# Dynamixel.net
KiCad netlist of a schematic drawn in EAGLE
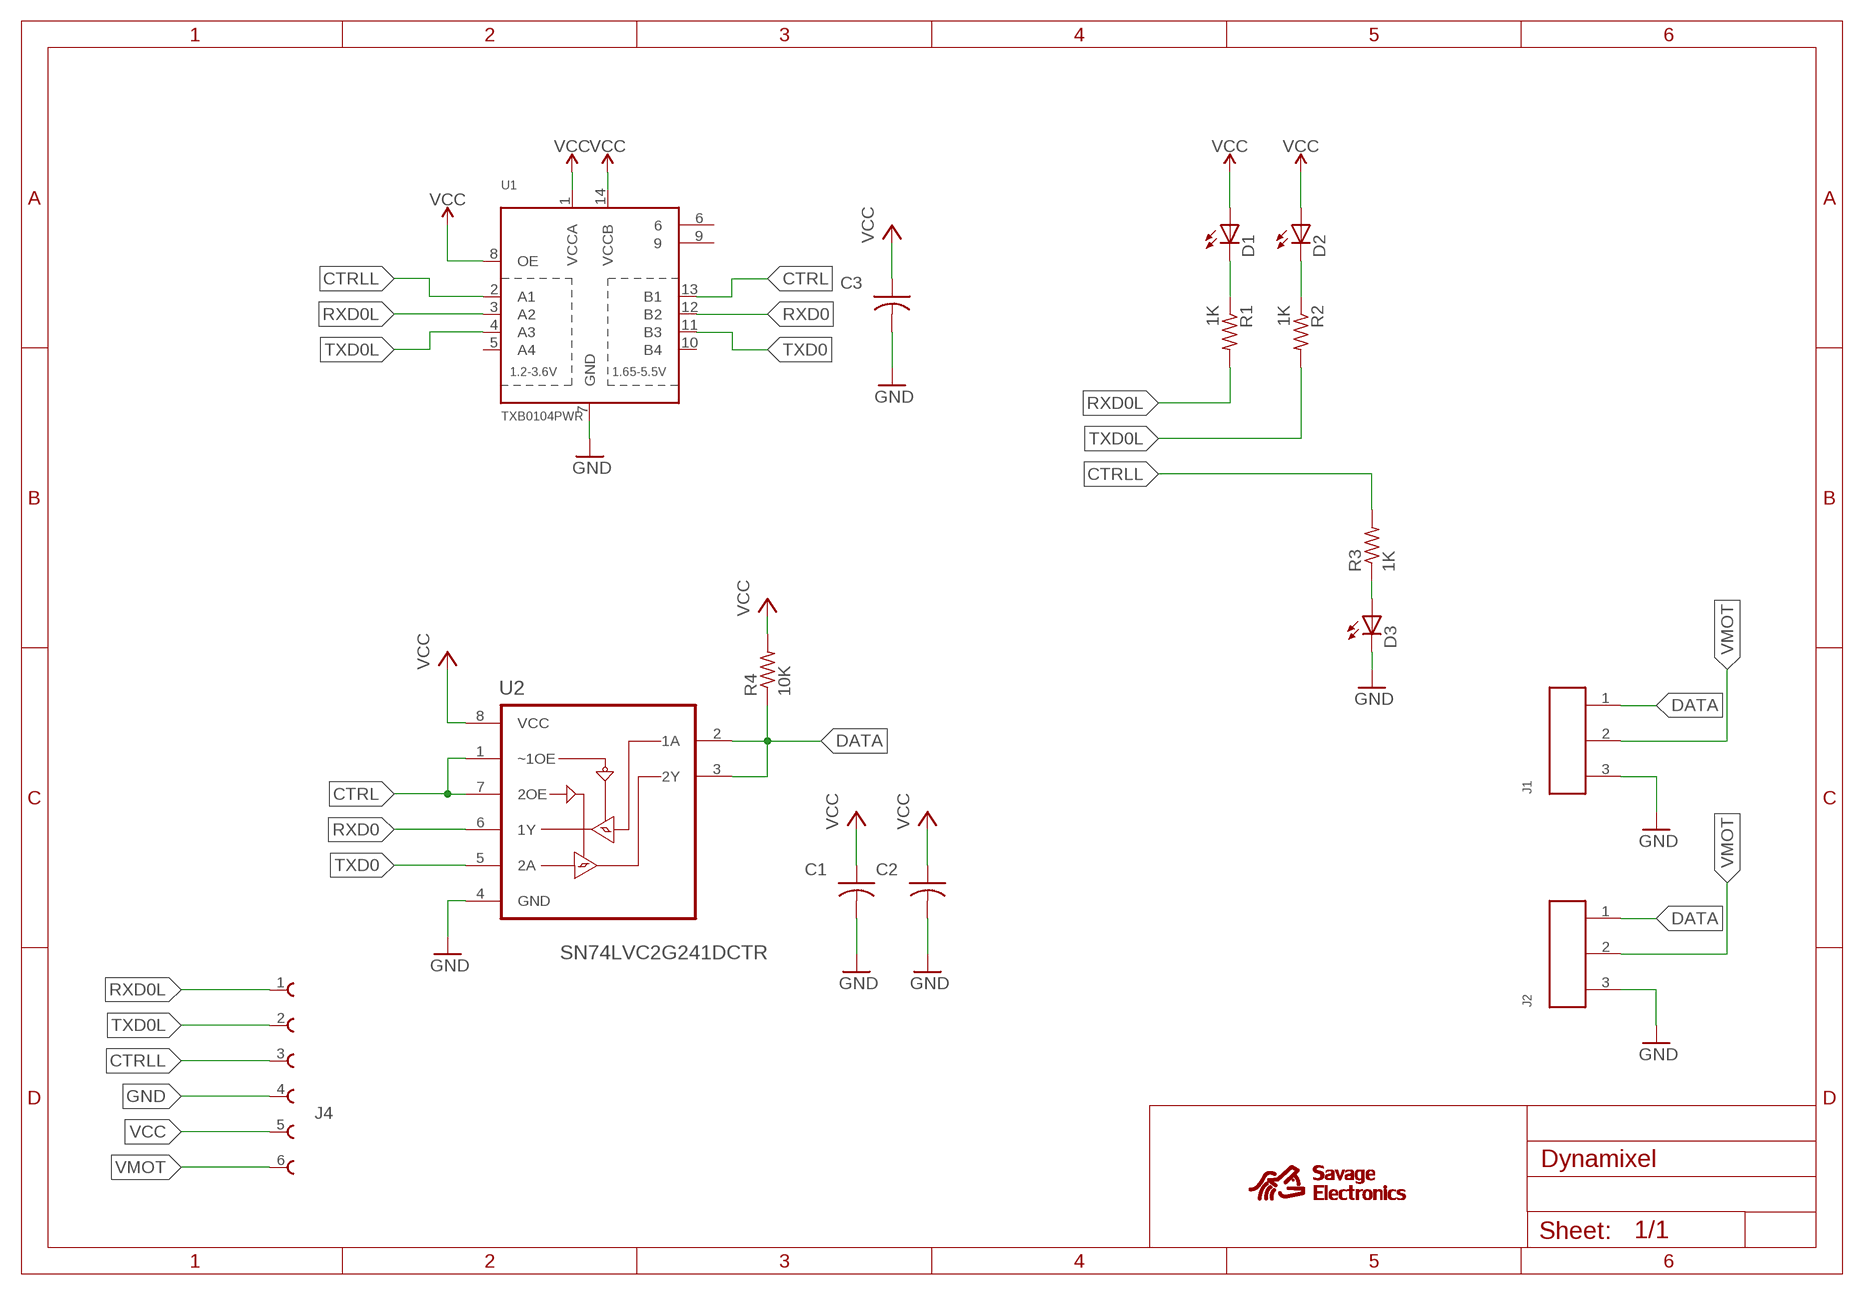
[diagram p0: schematic, sheet 1]

(export (version "E")
  (design (tool "Eeschema 10.0.6"))
  (components
    (comp (ref "C1")
      (value "1uF")
      (footprint "eagle-import:C0805")
      (libsource (lib "eagle-import") (part "C-USC0805"))
    )
    (comp (ref "C2")
      (value "1uF")
      (footprint "eagle-import:C0805")
      (libsource (lib "eagle-import") (part "C-USC0805"))
    )
    (comp (ref "C3")
      (value "1uF")
      (footprint "eagle-import:C0805")
      (libsource (lib "eagle-import") (part "C-USC0805"))
    )
    (comp (ref "D1")
      (value "LEDCHIP-LED0805")
      (footprint "eagle-import:CHIP-LED0805")
      (libsource (lib "eagle-import") (part "LEDCHIP-LED0805"))
    )
    (comp (ref "D2")
      (value "LEDCHIP-LED0805")
      (footprint "eagle-import:CHIP-LED0805")
      (libsource (lib "eagle-import") (part "LEDCHIP-LED0805"))
    )
    (comp (ref "D3")
      (value "LEDCHIP-LED0805")
      (footprint "eagle-import:CHIP-LED0805")
      (libsource (lib "eagle-import") (part "LEDCHIP-LED0805"))
    )
    (comp (ref "J1")
      (value "62000311722")
      (footprint "eagle-import:62000311722")
      (libsource (lib "eagle-import") (part "62000311722"))
    )
    (comp (ref "J2")
      (value "64600311622")
      (footprint "eagle-import:64600311622")
      (libsource (lib "eagle-import") (part "64600311622"))
    )
    (comp (ref "J4")
      (value "61300611121")
      (footprint "eagle-import:61300611121")
      (libsource (lib "eagle-import") (part "61300611121"))
    )
    (comp (ref "R1")
      (value "1K")
      (footprint "eagle-import:R0805")
      (libsource (lib "eagle-import") (part "R-US_R0805"))
    )
    (comp (ref "R2")
      (value "1K")
      (footprint "eagle-import:R0805")
      (libsource (lib "eagle-import") (part "R-US_R0805"))
    )
    (comp (ref "R3")
      (value "1K")
      (footprint "eagle-import:R0805")
      (libsource (lib "eagle-import") (part "R-US_R0805"))
    )
    (comp (ref "R4")
      (value "10K")
      (footprint "eagle-import:R0805")
      (libsource (lib "eagle-import") (part "R-US_R0805"))
    )
    (comp (ref "U$2")
      (value "SE_SMALL_SILK")
      (footprint "eagle-import:SE_SMALL_SILK")
      (libsource (lib "eagle-import") (part "SE_SMALL_SILK"))
    )
    (comp (ref "U$3")
      (value "SE_SMALL_FSILK")
      (footprint "eagle-import:SE_SMALL_FACESILK")
      (libsource (lib "eagle-import") (part "SE_SMALL_FSILK"))
    )
    (comp (ref "U1")
      (value "TXB0104PWR")
      (footprint "eagle-import:TSSOP14")
      (libsource (lib "eagle-import") (part "TXB0104PWR"))
    )
    (comp (ref "U2")
      (value "SN74LVC2G241DCTR")
      (footprint "eagle-import:SOP65P400X130-8N")
      (fields (field (name "MF") "Texas Instruments") (field (name "MP") "SN74LVC2G241"))
      (libsource (lib "eagle-import") (part "SN74LVC2G241"))
    )
  )
  (nets
    (net (code "1") (name "CTRL") (class "Default")
      (node (ref "U1") (pin "13") (pinfunction "B1_13") (pintype "bidirectional"))
      (node (ref "U2") (pin "1") (pinfunction "~{1OE}_1") (pintype "input"))
      (node (ref "U2") (pin "7") (pinfunction "2OE_7") (pintype "input"))
    )
    (net (code "2") (name "CTRLL") (class "Default")
      (node (ref "J4") (pin "3") (pinfunction "3_3") (pintype "passive"))
      (node (ref "R3") (pin "2") (pinfunction "2_2") (pintype "passive"))
      (node (ref "U1") (pin "2") (pinfunction "A1_2") (pintype "bidirectional"))
    )
    (net (code "3") (name "DATA") (class "Default")
      (node (ref "J1") (pin "1") (pinfunction "1_1") (pintype "passive"))
      (node (ref "J2") (pin "1") (pinfunction "1_1") (pintype "passive"))
      (node (ref "R4") (pin "1") (pinfunction "1_1") (pintype "passive"))
      (node (ref "U2") (pin "2") (pinfunction "1A_2") (pintype "input"))
      (node (ref "U2") (pin "3") (pinfunction "2Y_3") (pintype "output"))
    )
    (net (code "4") (name "GND") (class "Default")
      (node (ref "C1") (pin "2") (pinfunction "2_2") (pintype "passive"))
      (node (ref "C2") (pin "2") (pinfunction "2_2") (pintype "passive"))
      (node (ref "C3") (pin "2") (pinfunction "2_2") (pintype "passive"))
      (node (ref "D3") (pin "C") (pinfunction "C_C") (pintype "passive"))
      (node (ref "J1") (pin "3") (pinfunction "3_3") (pintype "passive"))
      (node (ref "J2") (pin "3") (pinfunction "3_3") (pintype "passive"))
      (node (ref "J4") (pin "4") (pinfunction "4_4") (pintype "passive"))
      (node (ref "U1") (pin "7") (pinfunction "GND_7") (pintype "bidirectional"))
      (node (ref "U2") (pin "4") (pinfunction "GND_4") (pintype "passive"))
    )
    (net (code "5") (name "Net-(D1-PadC)") (class "Default")
      (node (ref "D1") (pin "C") (pinfunction "C_C") (pintype "passive"))
      (node (ref "R1") (pin "1") (pinfunction "1_1") (pintype "passive"))
    )
    (net (code "6") (name "Net-(D2-PadC)") (class "Default")
      (node (ref "D2") (pin "C") (pinfunction "C_C") (pintype "passive"))
      (node (ref "R2") (pin "1") (pinfunction "1_1") (pintype "passive"))
    )
    (net (code "7") (name "Net-(D3-PadA)") (class "Default")
      (node (ref "D3") (pin "A") (pinfunction "A_A") (pintype "passive"))
      (node (ref "R3") (pin "1") (pinfunction "1_1") (pintype "passive"))
    )
    (net (code "8") (name "RXD0") (class "Default")
      (node (ref "U1") (pin "12") (pinfunction "B2_12") (pintype "bidirectional"))
      (node (ref "U2") (pin "6") (pinfunction "1Y_6") (pintype "output"))
    )
    (net (code "9") (name "RXD0L") (class "Default")
      (node (ref "J4") (pin "1") (pinfunction "1_1") (pintype "passive"))
      (node (ref "R1") (pin "2") (pinfunction "2_2") (pintype "passive"))
      (node (ref "U1") (pin "3") (pinfunction "A2_3") (pintype "bidirectional"))
    )
    (net (code "10") (name "TXD0") (class "Default")
      (node (ref "U1") (pin "11") (pinfunction "B3_11") (pintype "bidirectional"))
      (node (ref "U2") (pin "5") (pinfunction "2A_5") (pintype "input"))
    )
    (net (code "11") (name "TXD0L") (class "Default")
      (node (ref "J4") (pin "2") (pinfunction "2_2") (pintype "passive"))
      (node (ref "R2") (pin "2") (pinfunction "2_2") (pintype "passive"))
      (node (ref "U1") (pin "4") (pinfunction "A3_4") (pintype "bidirectional"))
    )
    (net (code "12") (name "VCC") (class "Default")
      (node (ref "C1") (pin "1") (pinfunction "1_1") (pintype "passive"))
      (node (ref "C2") (pin "1") (pinfunction "1_1") (pintype "passive"))
      (node (ref "C3") (pin "1") (pinfunction "1_1") (pintype "passive"))
      (node (ref "D1") (pin "A") (pinfunction "A_A") (pintype "passive"))
      (node (ref "D2") (pin "A") (pinfunction "A_A") (pintype "passive"))
      (node (ref "J4") (pin "5") (pinfunction "5_5") (pintype "passive"))
      (node (ref "R4") (pin "2") (pinfunction "2_2") (pintype "passive"))
      (node (ref "U1") (pin "1") (pinfunction "VCCA_1") (pintype "bidirectional"))
      (node (ref "U1") (pin "14") (pinfunction "VCCB_14") (pintype "bidirectional"))
      (node (ref "U1") (pin "8") (pinfunction "OE_8") (pintype "bidirectional"))
      (node (ref "U2") (pin "8") (pinfunction "VCC_8") (pintype "power_in"))
    )
    (net (code "13") (name "VMOT") (class "Default")
      (node (ref "J1") (pin "2") (pinfunction "2_2") (pintype "passive"))
      (node (ref "J2") (pin "2") (pinfunction "2_2") (pintype "passive"))
      (node (ref "J4") (pin "6") (pinfunction "6_6") (pintype "passive"))
    )
    (net (code "14") (name "unconnected-(U1-A4-Pad5)") (class "Default")
      (node (ref "U1") (pin "5") (pinfunction "A4_5") (pintype "bidirectional"))
    )
    (net (code "15") (name "unconnected-(U1-B4-Pad10)") (class "Default")
      (node (ref "U1") (pin "10") (pinfunction "B4_10") (pintype "bidirectional"))
    )
    (net (code "16") (name "unconnected-(U1-Pad6)") (class "Default")
      (node (ref "U1") (pin "6") (pinfunction "6_6") (pintype "bidirectional"))
    )
    (net (code "17") (name "unconnected-(U1-Pad9)") (class "Default")
      (node (ref "U1") (pin "9") (pinfunction "9_9") (pintype "bidirectional"))
    )
  )
)
